# SWDPort.net
KiCad netlist of a schematic drawn in Altium Designer
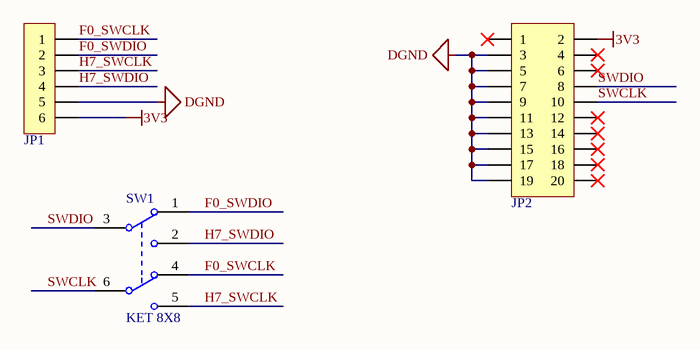
[diagram p0: SWDPort.SchDoc]

(export (version "E")
  (design (tool "Eeschema 10.0.6"))
  (components
    (comp (ref "JP1")
      (value "HDR-1X6")
      (footprint "MX 1.25-WS-6P")
      (description "6P接插件")
      (fields (field (name "版权归属") "源创客"))
      (libsource (lib "4.2   - 接插件-脚距1.25") (part "Header 6"))
    )
    (comp (ref "JP2")
      (value "Header 2X10")
      (footprint "HDR2.54-LI-2x10P")
      (description "10*2P接插件")
      (fields (field (name "版权归属") "源创客"))
      (libsource (lib "4.5   - 接插件-脚距2.54") (part "Header 10X2"))
    )
    (comp (ref "SW1")
      (value "KET 8X8")
      (footprint "KFT DIP-8X8")
      (description "8*8自锁开关")
      (fields (field (name "版权归属") "源创客"))
      (libsource (lib "5.1   - 按键-开关") (part "KET 8X8"))
    )
  )
  (nets
    (net (code "1") (name "/F0_SWCLK") (class "Default")
      (node (ref "JP1") (pin "1") (pinfunction "1_1") (pintype "passive"))
      (node (ref "SW1") (pin "4") (pinfunction "NO2_4") (pintype "passive"))
    )
    (net (code "2") (name "/F0_SWDIO") (class "Default")
      (node (ref "JP1") (pin "2") (pinfunction "2_2") (pintype "passive"))
      (node (ref "SW1") (pin "1") (pinfunction "NC1_1") (pintype "passive"))
    )
    (net (code "3") (name "/H7_SWCLK") (class "Default")
      (node (ref "JP1") (pin "3") (pinfunction "3_3") (pintype "passive"))
      (node (ref "SW1") (pin "5") (pinfunction "COM2_5") (pintype "passive"))
    )
    (net (code "4") (name "/H7_SWDIO") (class "Default")
      (node (ref "JP1") (pin "4") (pinfunction "4_4") (pintype "passive"))
      (node (ref "SW1") (pin "2") (pinfunction "COM2_2") (pintype "passive"))
    )
    (net (code "5") (name "/SWCLK") (class "Default")
      (node (ref "JP2") (pin "10") (pinfunction "10_10") (pintype "passive"))
      (node (ref "SW1") (pin "6") (pinfunction "NC2_6") (pintype "passive"))
    )
    (net (code "6") (name "/SWDIO") (class "Default")
      (node (ref "JP2") (pin "8") (pinfunction "8_8") (pintype "passive"))
      (node (ref "SW1") (pin "3") (pinfunction "NO1_3") (pintype "passive"))
    )
    (net (code "7") (name "3V3") (class "Default")
      (node (ref "JP1") (pin "6") (pinfunction "6_6") (pintype "passive"))
      (node (ref "JP2") (pin "2") (pinfunction "2_2") (pintype "passive"))
    )
    (net (code "8") (name "DGND") (class "Default")
      (node (ref "JP1") (pin "5") (pinfunction "5_5") (pintype "passive"))
      (node (ref "JP2") (pin "11") (pinfunction "11_11") (pintype "passive"))
      (node (ref "JP2") (pin "13") (pinfunction "13_13") (pintype "passive"))
      (node (ref "JP2") (pin "15") (pinfunction "15_15") (pintype "passive"))
      (node (ref "JP2") (pin "17") (pinfunction "17_17") (pintype "passive"))
      (node (ref "JP2") (pin "19") (pinfunction "19_19") (pintype "passive"))
      (node (ref "JP2") (pin "3") (pinfunction "3_3") (pintype "passive"))
      (node (ref "JP2") (pin "5") (pinfunction "5_5") (pintype "passive"))
      (node (ref "JP2") (pin "7") (pinfunction "7_7") (pintype "passive"))
      (node (ref "JP2") (pin "9") (pinfunction "9_9") (pintype "passive"))
    )
    (net (code "9") (name "unconnected-(JP2-Pad1)") (class "Default")
      (node (ref "JP2") (pin "1") (pinfunction "1_1") (pintype "passive+no_connect"))
    )
    (net (code "10") (name "unconnected-(JP2-Pad4)") (class "Default")
      (node (ref "JP2") (pin "4") (pinfunction "4_4") (pintype "passive+no_connect"))
    )
    (net (code "11") (name "unconnected-(JP2-Pad6)") (class "Default")
      (node (ref "JP2") (pin "6") (pinfunction "6_6") (pintype "passive+no_connect"))
    )
    (net (code "12") (name "unconnected-(JP2-Pad12)") (class "Default")
      (node (ref "JP2") (pin "12") (pinfunction "12_12") (pintype "passive+no_connect"))
    )
    (net (code "13") (name "unconnected-(JP2-Pad14)") (class "Default")
      (node (ref "JP2") (pin "14") (pinfunction "14_14") (pintype "passive+no_connect"))
    )
    (net (code "14") (name "unconnected-(JP2-Pad16)") (class "Default")
      (node (ref "JP2") (pin "16") (pinfunction "16_16") (pintype "passive+no_connect"))
    )
    (net (code "15") (name "unconnected-(JP2-Pad18)") (class "Default")
      (node (ref "JP2") (pin "18") (pinfunction "18_18") (pintype "passive+no_connect"))
    )
    (net (code "16") (name "unconnected-(JP2-Pad20)") (class "Default")
      (node (ref "JP2") (pin "20") (pinfunction "20_20") (pintype "passive+no_connect"))
    )
  )
)
